# AF_AMP.net
KiCad netlist of a schematic drawn in Altium Designer
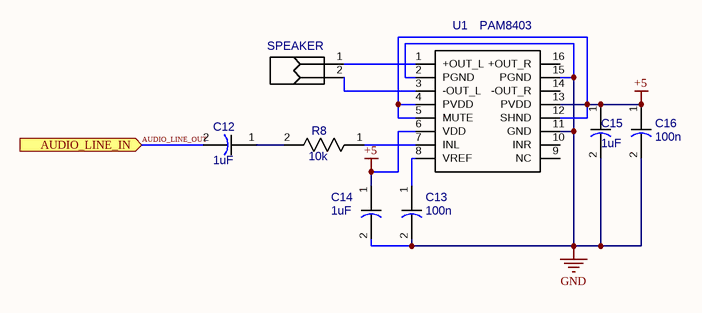
[diagram p0: AF AMP.SchDoc]

(export (version "E")
  (design (tool "Eeschema 10.0.6"))
  (components
    (comp (ref "C12")
      (value "1uF")
      (footprint "CAP_0805")
      (description "CAP_0805")
      (libsource (lib "*") (part "CAP_0805"))
    )
    (comp (ref "C13")
      (value "100n")
      (footprint "CAP_0805")
      (description "CAP_0805")
      (libsource (lib "*") (part "CAP_0805"))
    )
    (comp (ref "C14")
      (value "1uF")
      (footprint "CAP_0805")
      (description "CAP_0805")
      (libsource (lib "*") (part "CAP_0805"))
    )
    (comp (ref "C15")
      (value "1uF")
      (footprint "CAP_0805")
      (description "CAP_0805")
      (libsource (lib "*") (part "CAP_0805"))
    )
    (comp (ref "C16")
      (value "100n")
      (footprint "CAP_0805")
      (description "CAP_0805")
      (libsource (lib "*") (part "CAP_0805"))
    )
    (comp (ref "R8")
      (value "10k")
      (footprint "RES_0805")
      (description "RES_0805")
      (libsource (lib "*") (part "RES_0805"))
    )
    (comp (ref "SPEAKER")
      (value "~")
      (footprint "51022-0200")
      (description "51022-0200")
      (libsource (lib "*") (part "51022-0200"))
    )
    (comp (ref "U1") (value "PAM8403") (footprint "PAM8403") (libsource (lib "*") (part "PAM8403")))
  )
  (nets
    (net (code "1") (name "+5") (class "Default")
      (node (ref "C14") (pin "1") (pinfunction "1_1") (pintype "passive"))
      (node (ref "C15") (pin "1") (pinfunction "1_1") (pintype "passive"))
      (node (ref "C16") (pin "1") (pinfunction "1_1") (pintype "passive"))
      (node (ref "U1") (pin "12") (pinfunction "SHND_12") (pintype "passive"))
      (node (ref "U1") (pin "13") (pinfunction "PVDD_13") (pintype "passive"))
      (node (ref "U1") (pin "4") (pinfunction "PVDD_4") (pintype "passive"))
      (node (ref "U1") (pin "5") (pinfunction "MUTE_5") (pintype "passive"))
      (node (ref "U1") (pin "6") (pinfunction "VDD_6") (pintype "passive"))
    )
    (net (code "2") (name "/AUDIO_LINE_OUT") (class "Default")
      (node (ref "C12") (pin "2") (pinfunction "2_2") (pintype "passive"))
    )
    (net (code "3") (name "GND") (class "Default")
      (node (ref "C13") (pin "2") (pinfunction "2_2") (pintype "passive"))
      (node (ref "C14") (pin "2") (pinfunction "2_2") (pintype "passive"))
      (node (ref "C15") (pin "2") (pinfunction "2_2") (pintype "passive"))
      (node (ref "C16") (pin "2") (pinfunction "2_2") (pintype "passive"))
      (node (ref "U1") (pin "11") (pinfunction "GND_11") (pintype "passive"))
      (node (ref "U1") (pin "15") (pinfunction "PGND_15") (pintype "passive"))
      (node (ref "U1") (pin "2") (pinfunction "PGND_2") (pintype "passive"))
    )
    (net (code "4") (name "Net-(C12-Pad1)") (class "Default")
      (node (ref "C12") (pin "1") (pinfunction "1_1") (pintype "passive"))
      (node (ref "R8") (pin "2") (pinfunction "2_2") (pintype "passive"))
    )
    (net (code "5") (name "Net-(U1-+OUT_L)") (class "Default")
      (node (ref "SPEAKER") (pin "1") (pinfunction "1_1") (pintype "passive"))
      (node (ref "U1") (pin "1") (pinfunction "+OUT_L_1") (pintype "passive"))
    )
    (net (code "6") (name "Net-(U1--OUT_L)") (class "Default")
      (node (ref "SPEAKER") (pin "2") (pinfunction "2_2") (pintype "passive"))
      (node (ref "U1") (pin "3") (pinfunction "-OUT_L_3") (pintype "passive"))
    )
    (net (code "7") (name "Net-(U1-INL)") (class "Default")
      (node (ref "R8") (pin "1") (pinfunction "1_1") (pintype "passive"))
      (node (ref "U1") (pin "7") (pinfunction "INL_7") (pintype "passive"))
    )
    (net (code "8") (name "Net-(U1-VREF)") (class "Default")
      (node (ref "C13") (pin "1") (pinfunction "1_1") (pintype "passive"))
      (node (ref "U1") (pin "8") (pinfunction "VREF_8") (pintype "passive"))
    )
    (net (code "9") (name "unconnected-(U1-+OUT_R-Pad16)") (class "Default")
      (node (ref "U1") (pin "16") (pinfunction "+OUT_R_16") (pintype "passive"))
    )
    (net (code "10") (name "unconnected-(U1--OUT_R-Pad14)") (class "Default")
      (node (ref "U1") (pin "14") (pinfunction "-OUT_R_14") (pintype "passive"))
    )
    (net (code "11") (name "unconnected-(U1-INR-Pad10)") (class "Default")
      (node (ref "U1") (pin "10") (pinfunction "INR_10") (pintype "passive"))
    )
    (net (code "12") (name "unconnected-(U1-NC-Pad9)") (class "Default")
      (node (ref "U1") (pin "9") (pinfunction "NC_9") (pintype "passive"))
    )
  )
)
